# TK514_Interrupter.net
KiCad netlist of a schematic drawn in Altium Designer
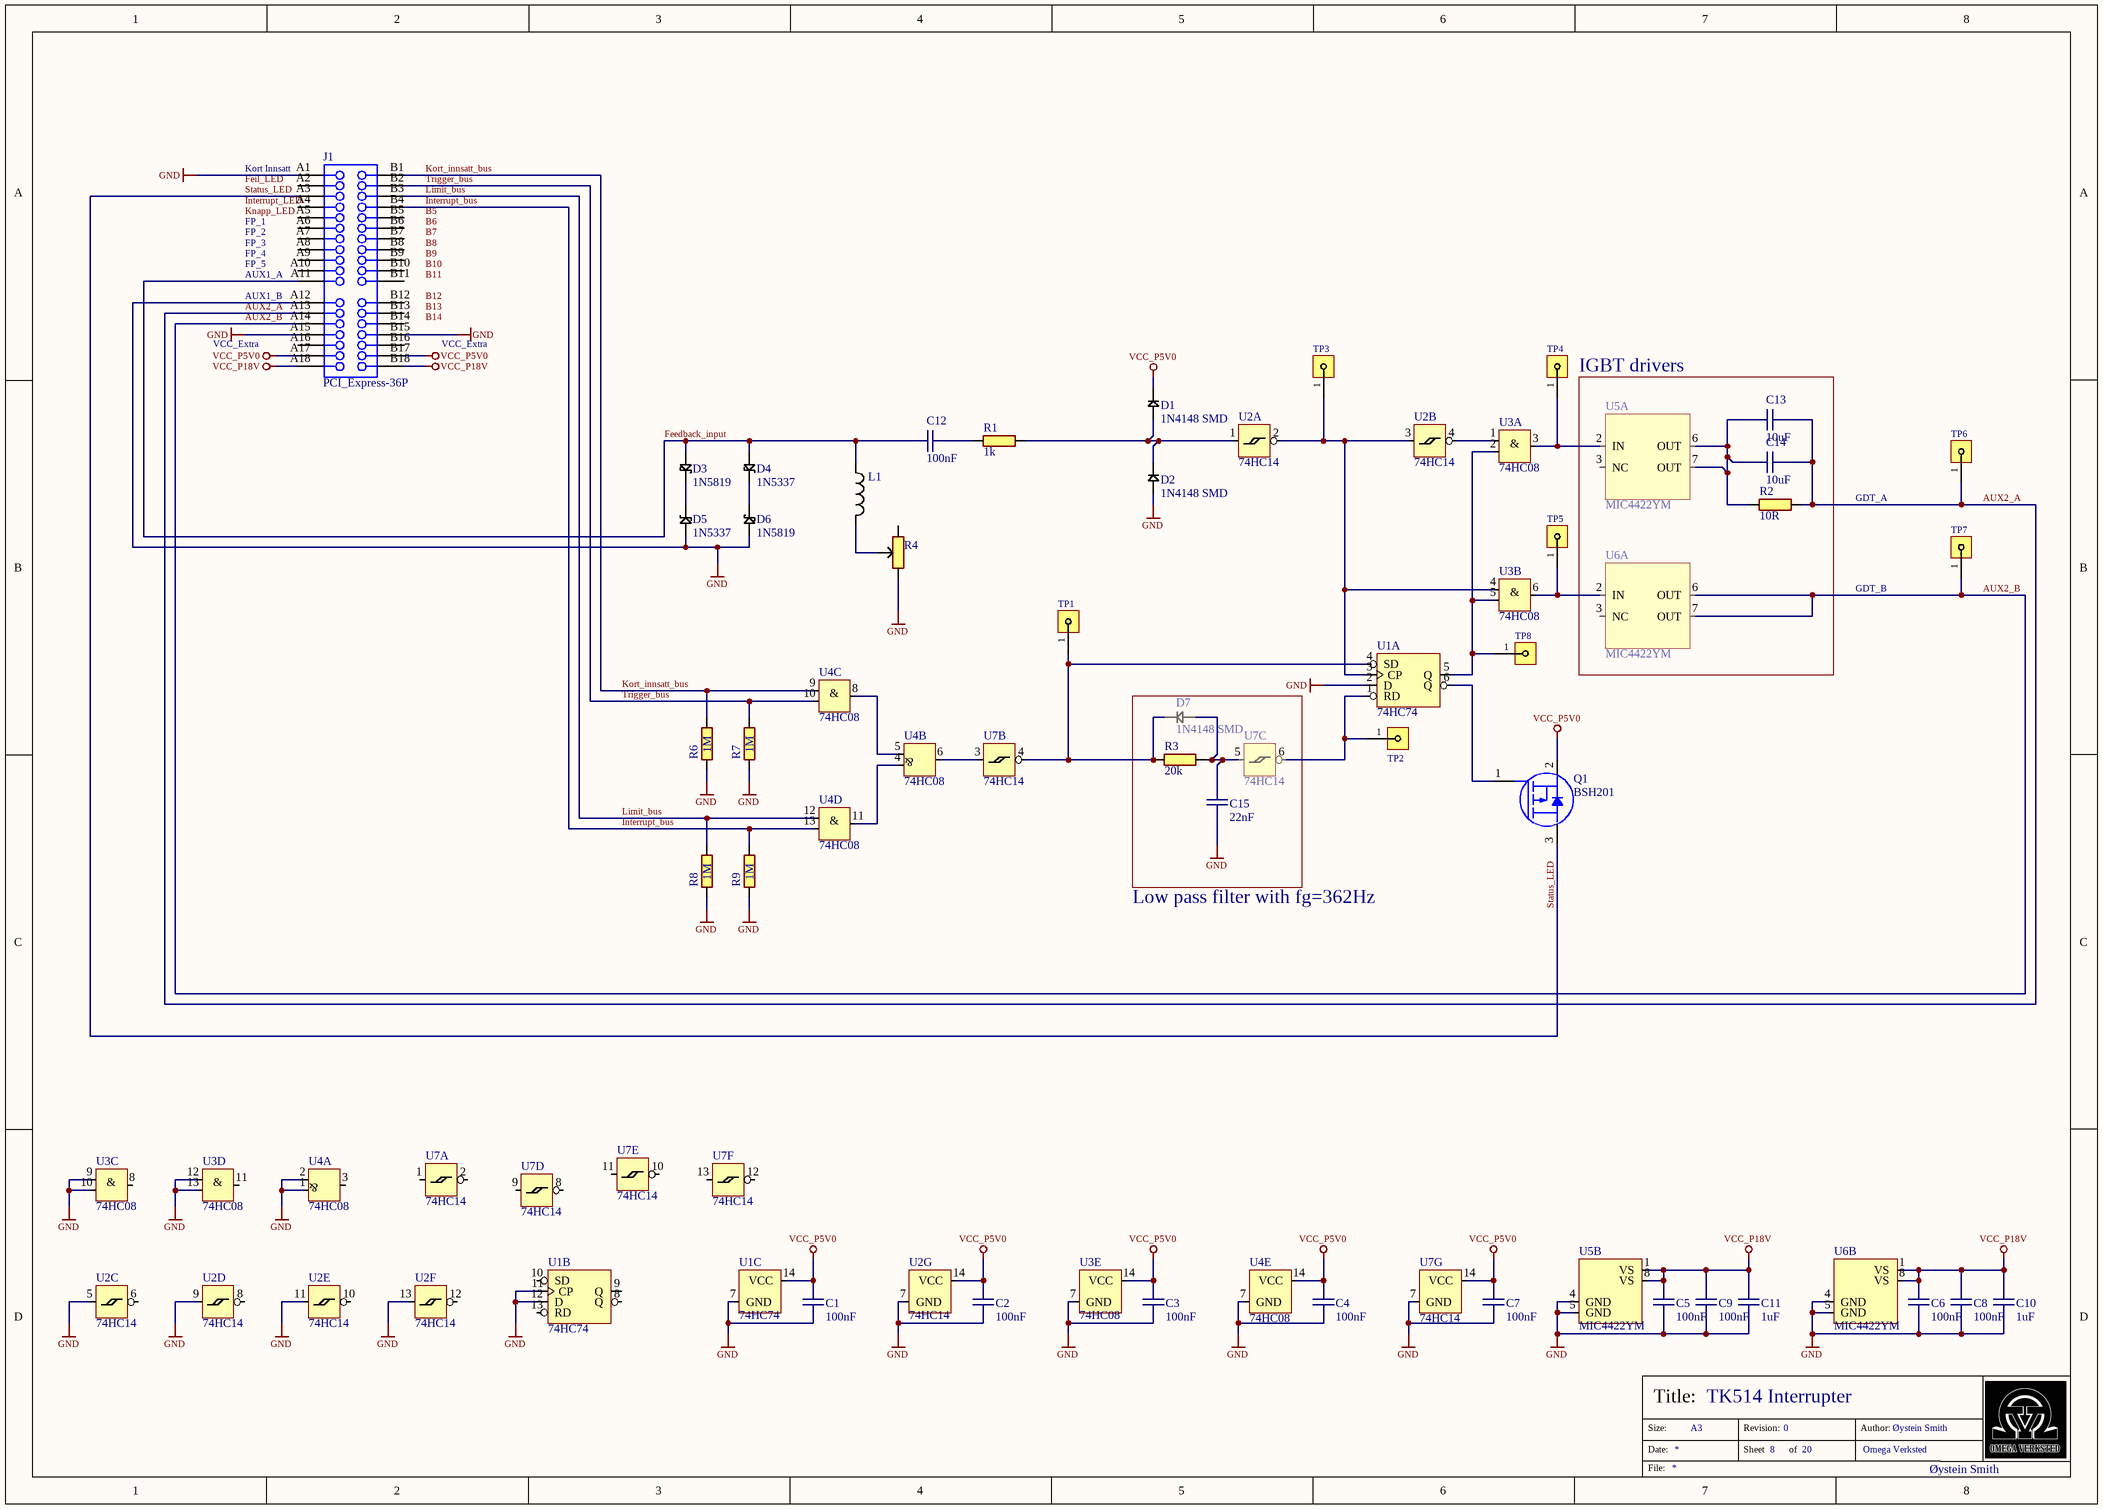
[diagram p0: TK514_Interrupter.SchDoc]

(export (version "E")
  (design (tool "Eeschema 10.0.6"))
  (components
    (comp (ref "C1")
      (value "100nF")
      (footprint "CAPC0603(1608)55_N")
      (description "X7R 50V 5%")
      (libsource (lib "OVLib_64") (part "CAP"))
    )
    (comp (ref "C2")
      (value "100nF")
      (footprint "CAPC0603(1608)55_N")
      (description "X7R 50V 5%")
      (libsource (lib "OVLib_64") (part "CAP"))
    )
    (comp (ref "C3")
      (value "100nF")
      (footprint "CAPC0603(1608)55_N")
      (description "X7R 50V 5%")
      (libsource (lib "OVLib_64") (part "CAP"))
    )
    (comp (ref "C4")
      (value "100nF")
      (footprint "CAPC0603(1608)55_N")
      (description "X7R 50V 5%")
      (libsource (lib "OVLib_64") (part "CAP"))
    )
    (comp (ref "C5")
      (value "100nF")
      (footprint "CAPC0603(1608)55_N")
      (description "X7R 50V 5%")
      (libsource (lib "OVLib_64") (part "CAP"))
    )
    (comp (ref "C6")
      (value "100nF")
      (footprint "CAPC0603(1608)55_N")
      (description "X7R 50V 5%")
      (libsource (lib "OVLib_64") (part "CAP"))
    )
    (comp (ref "C7")
      (value "100nF")
      (footprint "CAPC0603(1608)55_N")
      (description "X7R 50V 5%")
      (libsource (lib "OVLib_64") (part "CAP"))
    )
    (comp (ref "C8")
      (value "100nF")
      (footprint "CAPC0603(1608)55_N")
      (description "X7R 50V 5%")
      (libsource (lib "OVLib_64") (part "CAP"))
    )
    (comp (ref "C9")
      (value "100nF")
      (footprint "CAPC0603(1608)55_N")
      (description "X7R 50V 5%")
      (libsource (lib "OVLib_64") (part "CAP"))
    )
    (comp (ref "C10")
      (value "1uF")
      (footprint "CAPC1206(3216)170_N")
      (description "X7R 50V")
      (libsource (lib "OVLib_64") (part "CAP"))
    )
    (comp (ref "C11")
      (value "1uF")
      (footprint "CAPC1206(3216)170_N")
      (description "X7R 50V")
      (libsource (lib "OVLib_64") (part "CAP"))
    )
    (comp (ref "C12")
      (value "100nF")
      (footprint "CAPC0603(1608)55_N")
      (description "X7R 50V 5%")
      (libsource (lib "OVLib_64") (part "CAP"))
    )
    (comp (ref "C13")
      (value "10uF")
      (footprint "CAPC1206(3216)170_N")
      (description "X5R 50V 10%")
      (libsource (lib "OVLib_64") (part "CAP"))
    )
    (comp (ref "C14")
      (value "10uF")
      (footprint "CAPC1206(3216)170_N")
      (description "X5R 50V 10%")
      (libsource (lib "OVLib_64") (part "CAP"))
    )
    (comp (ref "C15")
      (value "22nF")
      (footprint "CAPC0805(2012)100_N")
      (description "X7R 50V")
      (libsource (lib "OVLib_64") (part "CAP"))
    )
    (comp (ref "D1")
      (value "1N4148 SMD")
      (footprint "SOD123")
      (description "SMD signaldiode")
      (libsource (lib "OVLib_64") (part "Diode"))
    )
    (comp (ref "D2")
      (value "1N4148 SMD")
      (footprint "SOD123")
      (description "SMD signaldiode")
      (libsource (lib "OVLib_64") (part "Diode"))
    )
    (comp (ref "D3")
      (value "1N5819")
      (footprint "DO-41")
      (description "Schottkydiode, 1A, 40V")
      (libsource (lib "OVLib_64") (part "SchottkyDiode"))
    )
    (comp (ref "D4")
      (value "1N5337")
      (footprint "DO-29")
      (description "Zenerdiode 4.7V 5W")
      (libsource (lib "OVLib_64") (part "Zenerdiode"))
    )
    (comp (ref "D5")
      (value "1N5337")
      (footprint "DO-29")
      (description "Zenerdiode 4.7V 5W")
      (libsource (lib "OVLib_64") (part "Zenerdiode"))
    )
    (comp (ref "D6")
      (value "1N5819")
      (footprint "DO-41")
      (description "Schottkydiode, 1A, 40V")
      (libsource (lib "OVLib_64") (part "SchottkyDiode"))
    )
    (comp (ref "D7")
      (value "1N4148 SMD")
      (footprint "SOD123")
      (description "SMD signaldiode")
      (libsource (lib "OVLib_64") (part "Diode"))
    )
    (comp (ref "J1")
      (value "PCI_Express-36P")
      (footprint "PCIeX1-GF-2D-1000-1K-O36")
      (description "PCI express PCB kortkankonnektor")
      (libsource (lib "OVLib_64") (part "PCI_Express-36P"))
    )
    (comp (ref "L1")
      (value "Spole 15H")
      (footprint "INDP3225X20N")
      (description "Wirewound Inductor, 15 µH, 2.8 ohm, 20 MHz, 130 mA")
      (libsource (lib "OVLib_64") (part "IND_GENERIC"))
    )
    (comp (ref "Q1")
      (value "BSH201")
      (footprint "SOT23-3_N")
      (description "P-Channel MOSFET 300mA")
      (libsource (lib "OVLib_64") (part "MOSFET_P_GSD"))
    )
    (comp (ref "R1")
      (value "1k")
      (footprint "RESC0603(1608)_N")
      (description "0.1W 1% Thick film resistor")
      (libsource (lib "OVLib_64") (part "Resistor2"))
    )
    (comp (ref "R2")
      (value "10R")
      (footprint "RESC0805(2012)_N")
      (description "0.1W 1% Thick film resistor")
      (libsource (lib "OVLib_64") (part "Resistor2"))
    )
    (comp (ref "R3")
      (value "20k")
      (footprint "RESC0603(1608)_N")
      (description "0.1W 1% Thick film resistor")
      (libsource (lib "OVLib_64") (part "Resistor2"))
    )
    (comp (ref "R4")
      (value "Trimmepot 100ohm")
      (footprint "TRIMPOT_3006P")
      (description "15 turn, horizontal")
      (libsource (lib "OVLib_64") (part "Potmeter"))
    )
    (comp (ref "R6")
      (value "1M")
      (footprint "RESC0603(1608)_N")
      (description "0.1W 1% Thick film resistor")
      (libsource (lib "") (part "Resistor2_1"))
    )
    (comp (ref "R7")
      (value "1M")
      (footprint "RESC0603(1608)_N")
      (description "0.1W 1% Thick film resistor")
      (libsource (lib "") (part "Resistor2_1"))
    )
    (comp (ref "R8")
      (value "1M")
      (footprint "RESC0603(1608)_N")
      (description "0.1W 1% Thick film resistor")
      (libsource (lib "") (part "Resistor2_1"))
    )
    (comp (ref "R9")
      (value "1M")
      (footprint "RESC0603(1608)_N")
      (description "0.1W 1% Thick film resistor")
      (libsource (lib "") (part "Resistor2_1"))
    )
    (comp (ref "TP1")
      (value "Header1x1")
      (footprint "HDRV1W64P254_1X1_254X254X900B")
      (description "2,54mm pitch")
      (libsource (lib "OVLib_64") (part "Header1x1"))
    )
    (comp (ref "TP2")
      (value "Header1x1")
      (footprint "HDRV1W64P254_1X1_254X254X900B")
      (description "2,54mm pitch")
      (libsource (lib "") (part "Header1x1_1"))
    )
    (comp (ref "TP3")
      (value "Header1x1")
      (footprint "HDRV1W64P254_1X1_254X254X900B")
      (description "2,54mm pitch")
      (libsource (lib "OVLib_64") (part "Header1x1"))
    )
    (comp (ref "TP4")
      (value "Header1x1")
      (footprint "HDRV1W64P254_1X1_254X254X900B")
      (description "2,54mm pitch")
      (libsource (lib "OVLib_64") (part "Header1x1"))
    )
    (comp (ref "TP5")
      (value "Header1x1")
      (footprint "HDRV1W64P254_1X1_254X254X900B")
      (description "2,54mm pitch")
      (libsource (lib "OVLib_64") (part "Header1x1"))
    )
    (comp (ref "TP6")
      (value "Header1x1")
      (footprint "HDRV1W64P254_1X1_254X254X900B")
      (description "2,54mm pitch")
      (libsource (lib "OVLib_64") (part "Header1x1"))
    )
    (comp (ref "TP7")
      (value "Header1x1")
      (footprint "HDRV1W64P254_1X1_254X254X900B")
      (description "2,54mm pitch")
      (libsource (lib "OVLib_64") (part "Header1x1"))
    )
    (comp (ref "TP8")
      (value "Header1x1")
      (footprint "HDRV1W64P254_1X1_254X254X900B")
      (description "2,54mm pitch")
      (libsource (lib "") (part "Header1x1_1"))
    )
    (comp (ref "U1")
      (value "74HC74")
      (footprint "SOIC-14")
      (description "Dual D flip flop")
      (libsource (lib "OVLib_64") (part "2XD-Flip-Flop"))
    )
    (comp (ref "U2")
      (value "74HC14")
      (footprint "SOIC-14")
      (description "Hex Schmitt trigger")
      (libsource (lib "OVLib_64") (part "6XSchmidt-Trigger"))
    )
    (comp (ref "U3")
      (value "74HC08")
      (footprint "SOIC-14")
      (description "Quad And Gate")
      (libsource (lib "") (part "4XAND-Gate_1"))
    )
    (comp (ref "U4")
      (value "74HC08")
      (footprint "SOIC-14")
      (description "Quad And Gate")
      (libsource (lib "") (part "4XAND-Gate_1"))
    )
    (comp (ref "U5")
      (value "MIC4422YM")
      (footprint "SOIC-8-WIDE")
      (description "Mosfet Driver")
      (libsource (lib "OVLib_64") (part "MIC4422YM"))
    )
    (comp (ref "U6")
      (value "MIC4422YM")
      (footprint "SOIC-8-WIDE")
      (description "Mosfet Driver")
      (libsource (lib "OVLib_64") (part "MIC4422YM"))
    )
    (comp (ref "U7")
      (value "74HC14")
      (footprint "SOIC-14")
      (description "Hex Schmitt trigger")
      (libsource (lib "OVLib_64") (part "6XSchmidt-Trigger"))
    )
  )
  (nets
    (net (code "1") (name "/AUX2_A") (class "Default")
      (node (ref "C13") (pin "2") (pinfunction "2_2") (pintype "passive"))
      (node (ref "C14") (pin "2") (pinfunction "2_2") (pintype "passive"))
      (node (ref "J1") (pin "A13") (pinfunction "A13_A13") (pintype "passive"))
      (node (ref "R2") (pin "2") (pinfunction "2_2") (pintype "passive"))
      (node (ref "TP6") (pin "1") (pinfunction "1_1") (pintype "passive"))
    )
    (net (code "2") (name "/AUX2_B") (class "Default")
      (node (ref "J1") (pin "A14") (pinfunction "A14_A14") (pintype "passive"))
      (node (ref "TP7") (pin "1") (pinfunction "1_1") (pintype "passive"))
      (node (ref "U6") (pin "6") (pinfunction "OUT_6") (pintype "passive"))
      (node (ref "U6") (pin "7") (pinfunction "OUT_7") (pintype "passive"))
    )
    (net (code "13") (name "/Feedback_input") (class "Default")
      (node (ref "C12") (pin "1") (pinfunction "1_1") (pintype "passive"))
      (node (ref "D3") (pin "1") (pinfunction "A_1") (pintype "passive"))
      (node (ref "D4") (pin "1") (pinfunction "A_1") (pintype "passive"))
      (node (ref "J1") (pin "A11") (pinfunction "A11_A11") (pintype "passive"))
      (node (ref "L1") (pin "1") (pinfunction "1_1") (pintype "passive"))
    )
    (net (code "16") (name "/Interrupt_bus") (class "Default")
      (node (ref "J1") (pin "B4") (pinfunction "B4_B4") (pintype "passive"))
      (node (ref "R9") (pin "2") (pinfunction "2_2") (pintype "passive"))
      (node (ref "U4") (pin "13") (pinfunction "13_13") (pintype "passive"))
    )
    (net (code "18") (name "/Kort_innsatt_bus") (class "Default")
      (node (ref "J1") (pin "B1") (pinfunction "B1_B1") (pintype "passive"))
      (node (ref "R6") (pin "2") (pinfunction "2_2") (pintype "passive"))
      (node (ref "U4") (pin "9") (pinfunction "9_9") (pintype "passive"))
    )
    (net (code "19") (name "/Limit_bus") (class "Default")
      (node (ref "J1") (pin "B3") (pinfunction "B3_B3") (pintype "passive"))
      (node (ref "R8") (pin "2") (pinfunction "2_2") (pintype "passive"))
      (node (ref "U4") (pin "12") (pinfunction "12_12") (pintype "passive"))
    )
    (net (code "20") (name "/Status_LED") (class "Default")
      (node (ref "J1") (pin "A3") (pinfunction "A3_A3") (pintype "passive"))
      (node (ref "Q1") (pin "3") (pinfunction "Drain_3") (pintype "passive"))
    )
    (net (code "21") (name "/Trigger_bus") (class "Default")
      (node (ref "J1") (pin "B2") (pinfunction "B2_B2") (pintype "passive"))
      (node (ref "R7") (pin "2") (pinfunction "2_2") (pintype "passive"))
      (node (ref "U4") (pin "10") (pinfunction "10_10") (pintype "passive"))
    )
    (net (code "22") (name "GND") (class "Default")
      (node (ref "C1") (pin "1") (pinfunction "1_1") (pintype "passive"))
      (node (ref "C10") (pin "1") (pinfunction "1_1") (pintype "passive"))
      (node (ref "C11") (pin "1") (pinfunction "1_1") (pintype "passive"))
      (node (ref "C15") (pin "1") (pinfunction "1_1") (pintype "passive"))
      (node (ref "C2") (pin "1") (pinfunction "1_1") (pintype "passive"))
      (node (ref "C3") (pin "1") (pinfunction "1_1") (pintype "passive"))
      (node (ref "C4") (pin "1") (pinfunction "1_1") (pintype "passive"))
      (node (ref "C5") (pin "1") (pinfunction "1_1") (pintype "passive"))
      (node (ref "C6") (pin "1") (pinfunction "1_1") (pintype "passive"))
      (node (ref "C7") (pin "1") (pinfunction "1_1") (pintype "passive"))
      (node (ref "C8") (pin "1") (pinfunction "1_1") (pintype "passive"))
      (node (ref "C9") (pin "1") (pinfunction "1_1") (pintype "passive"))
      (node (ref "D2") (pin "1") (pinfunction "A_1") (pintype "passive"))
      (node (ref "D5") (pin "1") (pinfunction "A_1") (pintype "passive"))
      (node (ref "D6") (pin "1") (pinfunction "A_1") (pintype "passive"))
      (node (ref "J1") (pin "A1") (pinfunction "A1_A1") (pintype "passive"))
      (node (ref "J1") (pin "A12") (pinfunction "A12_A12") (pintype "passive"))
      (node (ref "J1") (pin "A15") (pinfunction "A15_A15") (pintype "passive"))
      (node (ref "J1") (pin "B15") (pinfunction "B15_B15") (pintype "passive"))
      (node (ref "R4") (pin "1") (pinfunction "1_1") (pintype "passive"))
      (node (ref "R6") (pin "1") (pinfunction "1_1") (pintype "passive"))
      (node (ref "R7") (pin "1") (pinfunction "1_1") (pintype "passive"))
      (node (ref "R8") (pin "1") (pinfunction "1_1") (pintype "passive"))
      (node (ref "R9") (pin "1") (pinfunction "1_1") (pintype "passive"))
      (node (ref "U1") (pin "11") (pinfunction "CP_11") (pintype "passive"))
      (node (ref "U1") (pin "12") (pinfunction "D_12") (pintype "passive"))
      (node (ref "U1") (pin "2") (pinfunction "D_2") (pintype "passive"))
      (node (ref "U1") (pin "7") (pinfunction "GND_7") (pintype "passive"))
      (node (ref "U2") (pin "11") (pinfunction "11_11") (pintype "passive"))
      (node (ref "U2") (pin "13") (pinfunction "13_13") (pintype "passive"))
      (node (ref "U2") (pin "5") (pinfunction "5_5") (pintype "passive"))
      (node (ref "U2") (pin "7") (pinfunction "GND_7") (pintype "passive"))
      (node (ref "U2") (pin "9") (pinfunction "9_9") (pintype "passive"))
      (node (ref "U3") (pin "10") (pinfunction "10_10") (pintype "passive"))
      (node (ref "U3") (pin "12") (pinfunction "12_12") (pintype "passive"))
      (node (ref "U3") (pin "13") (pinfunction "13_13") (pintype "passive"))
      (node (ref "U3") (pin "7") (pinfunction "GND_7") (pintype "passive"))
      (node (ref "U3") (pin "9") (pinfunction "9_9") (pintype "passive"))
      (node (ref "U4") (pin "1") (pinfunction "1_1") (pintype "passive"))
      (node (ref "U4") (pin "2") (pinfunction "2_2") (pintype "passive"))
      (node (ref "U4") (pin "7") (pinfunction "GND_7") (pintype "passive"))
      (node (ref "U5") (pin "4") (pinfunction "GND_4") (pintype "passive"))
      (node (ref "U5") (pin "5") (pinfunction "GND_5") (pintype "passive"))
      (node (ref "U6") (pin "4") (pinfunction "GND_4") (pintype "passive"))
      (node (ref "U6") (pin "5") (pinfunction "GND_5") (pintype "passive"))
      (node (ref "U7") (pin "7") (pinfunction "GND_7") (pintype "passive"))
    )
    (net (code "23") (name "Net-(C12-Pad2)") (class "Default")
      (node (ref "C12") (pin "2") (pinfunction "2_2") (pintype "passive"))
      (node (ref "R1") (pin "1") (pinfunction "1_1") (pintype "passive"))
    )
    (net (code "24") (name "Net-(C13-Pad1)") (class "Default")
      (node (ref "C13") (pin "1") (pinfunction "1_1") (pintype "passive"))
      (node (ref "C14") (pin "1") (pinfunction "1_1") (pintype "passive"))
      (node (ref "R2") (pin "1") (pinfunction "1_1") (pintype "passive"))
      (node (ref "U5") (pin "6") (pinfunction "OUT_6") (pintype "passive"))
      (node (ref "U5") (pin "7") (pinfunction "OUT_7") (pintype "passive"))
    )
    (net (code "25") (name "Net-(D1-A)") (class "Default")
      (node (ref "D1") (pin "1") (pinfunction "A_1") (pintype "passive"))
      (node (ref "D2") (pin "2") (pinfunction "K_2") (pintype "passive"))
      (node (ref "R1") (pin "2") (pinfunction "2_2") (pintype "passive"))
      (node (ref "U2") (pin "1") (pinfunction "1_1") (pintype "passive"))
    )
    (net (code "26") (name "Net-(D3-K)") (class "Default")
      (node (ref "D3") (pin "2") (pinfunction "K_2") (pintype "passive"))
      (node (ref "D5") (pin "2") (pinfunction "K_2") (pintype "passive"))
    )
    (net (code "27") (name "Net-(D4-K)") (class "Default")
      (node (ref "D4") (pin "2") (pinfunction "K_2") (pintype "passive"))
      (node (ref "D6") (pin "2") (pinfunction "K_2") (pintype "passive"))
    )
    (net (code "28") (name "Net-(D7-A)") (class "Default")
      (node (ref "C15") (pin "2") (pinfunction "2_2") (pintype "passive"))
      (node (ref "D7") (pin "1") (pinfunction "A_1") (pintype "passive"))
      (node (ref "R3") (pin "2") (pinfunction "2_2") (pintype "passive"))
      (node (ref "U7") (pin "5") (pinfunction "5_5") (pintype "passive"))
    )
    (net (code "29") (name "Net-(D7-K)") (class "Default")
      (node (ref "D7") (pin "2") (pinfunction "K_2") (pintype "passive"))
      (node (ref "R3") (pin "1") (pinfunction "1_1") (pintype "passive"))
      (node (ref "TP1") (pin "1") (pinfunction "1_1") (pintype "passive"))
      (node (ref "U1") (pin "4") (pinfunction "SD_4") (pintype "passive"))
      (node (ref "U7") (pin "4") (pinfunction "4_4") (pintype "passive"))
    )
    (net (code "30") (name "Net-(L1-Pad2)") (class "Default")
      (node (ref "L1") (pin "2") (pinfunction "2_2") (pintype "passive"))
      (node (ref "R4") (pin "2") (pinfunction "2_2") (pintype "passive"))
    )
    (net (code "31") (name "Net-(Q1-Gate)") (class "Default")
      (node (ref "Q1") (pin "1") (pinfunction "Gate_1") (pintype "passive"))
      (node (ref "U1") (pin "6") (pinfunction "Q_6") (pintype "passive"))
    )
    (net (code "32") (name "Net-(TP8-Pad1)") (class "Default")
      (node (ref "TP8") (pin "1") (pinfunction "1_1") (pintype "passive"))
      (node (ref "U1") (pin "5") (pinfunction "Q_5") (pintype "passive"))
      (node (ref "U3") (pin "2") (pinfunction "2_2") (pintype "passive"))
      (node (ref "U3") (pin "5") (pinfunction "5_5") (pintype "passive"))
    )
    (net (code "33") (name "Net-(U1A-CP)") (class "Default")
      (node (ref "TP3") (pin "1") (pinfunction "1_1") (pintype "passive"))
      (node (ref "U1") (pin "3") (pinfunction "CP_3") (pintype "passive"))
      (node (ref "U2") (pin "2") (pinfunction "2_2") (pintype "passive"))
      (node (ref "U2") (pin "3") (pinfunction "3_3") (pintype "passive"))
      (node (ref "U3") (pin "4") (pinfunction "4_4") (pintype "passive"))
    )
    (net (code "34") (name "Net-(U1A-RD)") (class "Default")
      (node (ref "TP2") (pin "1") (pinfunction "1_1") (pintype "passive"))
      (node (ref "U1") (pin "1") (pinfunction "RD_1") (pintype "passive"))
      (node (ref "U7") (pin "6") (pinfunction "6_6") (pintype "passive"))
    )
    (net (code "35") (name "Net-(U2-Pad4)") (class "Default")
      (node (ref "U2") (pin "4") (pinfunction "4_4") (pintype "passive"))
      (node (ref "U3") (pin "1") (pinfunction "1_1") (pintype "passive"))
    )
    (net (code "36") (name "Net-(U4-Pad5)") (class "Default")
      (node (ref "U4") (pin "5") (pinfunction "5_5") (pintype "passive"))
      (node (ref "U4") (pin "8") (pinfunction "8_8") (pintype "passive"))
    )
    (net (code "37") (name "Net-(U4-Pad6)") (class "Default")
      (node (ref "U4") (pin "6") (pinfunction "6_6") (pintype "passive"))
      (node (ref "U7") (pin "3") (pinfunction "3_3") (pintype "passive"))
    )
    (net (code "38") (name "Net-(U4-Pad11)") (class "Default")
      (node (ref "U4") (pin "11") (pinfunction "11_11") (pintype "passive"))
      (node (ref "U4") (pin "4") (pinfunction "4_4") (pintype "passive"))
    )
    (net (code "39") (name "Net-(U5A-IN)") (class "Default")
      (node (ref "TP4") (pin "1") (pinfunction "1_1") (pintype "passive"))
      (node (ref "U3") (pin "3") (pinfunction "3_3") (pintype "passive"))
      (node (ref "U5") (pin "2") (pinfunction "IN_2") (pintype "passive"))
    )
    (net (code "40") (name "Net-(U6A-IN)") (class "Default")
      (node (ref "TP5") (pin "1") (pinfunction "1_1") (pintype "passive"))
      (node (ref "U3") (pin "6") (pinfunction "6_6") (pintype "passive"))
      (node (ref "U6") (pin "2") (pinfunction "IN_2") (pintype "passive"))
    )
    (net (code "41") (name "VCC_P5V0") (class "Default")
      (node (ref "C1") (pin "2") (pinfunction "2_2") (pintype "passive"))
      (node (ref "C2") (pin "2") (pinfunction "2_2") (pintype "passive"))
      (node (ref "C3") (pin "2") (pinfunction "2_2") (pintype "passive"))
      (node (ref "C4") (pin "2") (pinfunction "2_2") (pintype "passive"))
      (node (ref "C7") (pin "2") (pinfunction "2_2") (pintype "passive"))
      (node (ref "D1") (pin "2") (pinfunction "K_2") (pintype "passive"))
      (node (ref "J1") (pin "A17") (pinfunction "A17_A17") (pintype "passive"))
      (node (ref "J1") (pin "B17") (pinfunction "B17_B17") (pintype "passive"))
      (node (ref "Q1") (pin "2") (pinfunction "Source_2") (pintype "passive"))
      (node (ref "U1") (pin "14") (pinfunction "VCC_14") (pintype "passive"))
      (node (ref "U2") (pin "14") (pinfunction "VCC_14") (pintype "passive"))
      (node (ref "U3") (pin "14") (pinfunction "VCC_14") (pintype "passive"))
      (node (ref "U4") (pin "14") (pinfunction "VCC_14") (pintype "passive"))
      (node (ref "U7") (pin "14") (pinfunction "VCC_14") (pintype "passive"))
    )
    (net (code "42") (name "VCC_P18V") (class "Default")
      (node (ref "C10") (pin "2") (pinfunction "2_2") (pintype "passive"))
      (node (ref "C11") (pin "2") (pinfunction "2_2") (pintype "passive"))
      (node (ref "C5") (pin "2") (pinfunction "2_2") (pintype "passive"))
      (node (ref "C6") (pin "2") (pinfunction "2_2") (pintype "passive"))
      (node (ref "C8") (pin "2") (pinfunction "2_2") (pintype "passive"))
      (node (ref "C9") (pin "2") (pinfunction "2_2") (pintype "passive"))
      (node (ref "J1") (pin "A18") (pinfunction "A18_A18") (pintype "passive"))
      (node (ref "J1") (pin "B18") (pinfunction "B18_B18") (pintype "passive"))
      (node (ref "U5") (pin "1") (pinfunction "VS_1") (pintype "passive"))
      (node (ref "U5") (pin "8") (pinfunction "VS_8") (pintype "passive"))
      (node (ref "U6") (pin "1") (pinfunction "VS_1") (pintype "passive"))
      (node (ref "U6") (pin "8") (pinfunction "VS_8") (pintype "passive"))
    )
    (net (code "43") (name "unconnected-(J1-PadA2)") (class "Default")
      (node (ref "J1") (pin "A2") (pinfunction "A2_A2") (pintype "passive"))
    )
    (net (code "44") (name "unconnected-(J1-PadA4)") (class "Default")
      (node (ref "J1") (pin "A4") (pinfunction "A4_A4") (pintype "passive"))
    )
    (net (code "45") (name "unconnected-(J1-PadA5)") (class "Default")
      (node (ref "J1") (pin "A5") (pinfunction "A5_A5") (pintype "passive"))
    )
    (net (code "46") (name "unconnected-(J1-PadA6)") (class "Default")
      (node (ref "J1") (pin "A6") (pinfunction "A6_A6") (pintype "passive"))
    )
    (net (code "47") (name "unconnected-(J1-PadA7)") (class "Default")
      (node (ref "J1") (pin "A7") (pinfunction "A7_A7") (pintype "passive"))
    )
    (net (code "48") (name "unconnected-(J1-PadA8)") (class "Default")
      (node (ref "J1") (pin "A8") (pinfunction "A8_A8") (pintype "passive"))
    )
    (net (code "49") (name "unconnected-(J1-PadA9)") (class "Default")
      (node (ref "J1") (pin "A9") (pinfunction "A9_A9") (pintype "passive"))
    )
    (net (code "50") (name "unconnected-(J1-PadA10)") (class "Default")
      (node (ref "J1") (pin "A10") (pinfunction "A10_A10") (pintype "passive"))
    )
    (net (code "51") (name "unconnected-(J1-PadA16)") (class "Default")
      (node (ref "J1") (pin "A16") (pinfunction "A16_A16") (pintype "passive"))
    )
    (net (code "52") (name "unconnected-(J1-PadB5)") (class "Default")
      (node (ref "J1") (pin "B5") (pinfunction "B5_B5") (pintype "passive"))
    )
    (net (code "53") (name "unconnected-(J1-PadB6)") (class "Default")
      (node (ref "J1") (pin "B6") (pinfunction "B6_B6") (pintype "passive"))
    )
    (net (code "54") (name "unconnected-(J1-PadB7)") (class "Default")
      (node (ref "J1") (pin "B7") (pinfunction "B7_B7") (pintype "passive"))
    )
    (net (code "55") (name "unconnected-(J1-PadB8)") (class "Default")
      (node (ref "J1") (pin "B8") (pinfunction "B8_B8") (pintype "passive"))
    )
    (net (code "56") (name "unconnected-(J1-PadB9)") (class "Default")
      (node (ref "J1") (pin "B9") (pinfunction "B9_B9") (pintype "passive"))
    )
    (net (code "57") (name "unconnected-(J1-PadB10)") (class "Default")
      (node (ref "J1") (pin "B10") (pinfunction "B10_B10") (pintype "passive"))
    )
    (net (code "58") (name "unconnected-(J1-PadB11)") (class "Default")
      (node (ref "J1") (pin "B11") (pinfunction "B11_B11") (pintype "passive"))
    )
    (net (code "59") (name "unconnected-(J1-PadB12)") (class "Default")
      (node (ref "J1") (pin "B12") (pinfunction "B12_B12") (pintype "passive"))
    )
    (net (code "60") (name "unconnected-(J1-PadB13)") (class "Default")
      (node (ref "J1") (pin "B13") (pinfunction "B13_B13") (pintype "passive"))
    )
    (net (code "61") (name "unconnected-(J1-PadB14)") (class "Default")
      (node (ref "J1") (pin "B14") (pinfunction "B14_B14") (pintype "passive"))
    )
    (net (code "62") (name "unconnected-(J1-PadB16)") (class "Default")
      (node (ref "J1") (pin "B16") (pinfunction "B16_B16") (pintype "passive"))
    )
    (net (code "63") (name "unconnected-(R4-Pad3)") (class "Default")
      (node (ref "R4") (pin "3") (pinfunction "3_3") (pintype "passive"))
    )
    (net (code "64") (name "unconnected-(U1B-Q-Pad8)") (class "Default")
      (node (ref "U1") (pin "8") (pinfunction "Q_8") (pintype "passive"))
    )
    (net (code "65") (name "unconnected-(U1B-Q-Pad9)") (class "Default")
      (node (ref "U1") (pin "9") (pinfunction "Q_9") (pintype "passive"))
    )
    (net (code "66") (name "unconnected-(U1B-RD-Pad13)") (class "Default")
      (node (ref "U1") (pin "13") (pinfunction "RD_13") (pintype "passive"))
    )
    (net (code "67") (name "unconnected-(U1B-SD-Pad10)") (class "Default")
      (node (ref "U1") (pin "10") (pinfunction "SD_10") (pintype "passive"))
    )
    (net (code "68") (name "unconnected-(U2-Pad6)") (class "Default")
      (node (ref "U2") (pin "6") (pinfunction "6_6") (pintype "passive"))
    )
    (net (code "69") (name "unconnected-(U2-Pad8)") (class "Default")
      (node (ref "U2") (pin "8") (pinfunction "8_8") (pintype "passive"))
    )
    (net (code "70") (name "unconnected-(U2-Pad10)") (class "Default")
      (node (ref "U2") (pin "10") (pinfunction "10_10") (pintype "passive"))
    )
    (net (code "71") (name "unconnected-(U2-Pad12)") (class "Default")
      (node (ref "U2") (pin "12") (pinfunction "12_12") (pintype "passive"))
    )
    (net (code "72") (name "unconnected-(U3-Pad8)") (class "Default")
      (node (ref "U3") (pin "8") (pinfunction "8_8") (pintype "passive"))
    )
    (net (code "73") (name "unconnected-(U3-Pad11)") (class "Default")
      (node (ref "U3") (pin "11") (pinfunction "11_11") (pintype "passive"))
    )
    (net (code "74") (name "unconnected-(U4-Pad3)") (class "Default")
      (node (ref "U4") (pin "3") (pinfunction "3_3") (pintype "passive"))
    )
    (net (code "75") (name "unconnected-(U5A-NC-Pad3)") (class "Default")
      (node (ref "U5") (pin "3") (pinfunction "NC_3") (pintype "passive"))
    )
    (net (code "76") (name "unconnected-(U6A-NC-Pad3)") (class "Default")
      (node (ref "U6") (pin "3") (pinfunction "NC_3") (pintype "passive"))
    )
    (net (code "77") (name "unconnected-(U7-Pad1)") (class "Default")
      (node (ref "U7") (pin "1") (pinfunction "1_1") (pintype "passive"))
    )
    (net (code "78") (name "unconnected-(U7-Pad2)") (class "Default")
      (node (ref "U7") (pin "2") (pinfunction "2_2") (pintype "passive"))
    )
    (net (code "79") (name "unconnected-(U7-Pad8)") (class "Default")
      (node (ref "U7") (pin "8") (pinfunction "8_8") (pintype "passive"))
    )
    (net (code "80") (name "unconnected-(U7-Pad9)") (class "Default")
      (node (ref "U7") (pin "9") (pinfunction "9_9") (pintype "passive"))
    )
    (net (code "81") (name "unconnected-(U7-Pad10)") (class "Default")
      (node (ref "U7") (pin "10") (pinfunction "10_10") (pintype "passive"))
    )
    (net (code "82") (name "unconnected-(U7-Pad11)") (class "Default")
      (node (ref "U7") (pin "11") (pinfunction "11_11") (pintype "passive"))
    )
    (net (code "83") (name "unconnected-(U7-Pad12)") (class "Default")
      (node (ref "U7") (pin "12") (pinfunction "12_12") (pintype "passive"))
    )
    (net (code "84") (name "unconnected-(U7-Pad13)") (class "Default")
      (node (ref "U7") (pin "13") (pinfunction "13_13") (pintype "passive"))
    )
  )
)
